# OLM-jee-128.net
KiCad netlist of a schematic drawn in EAGLE
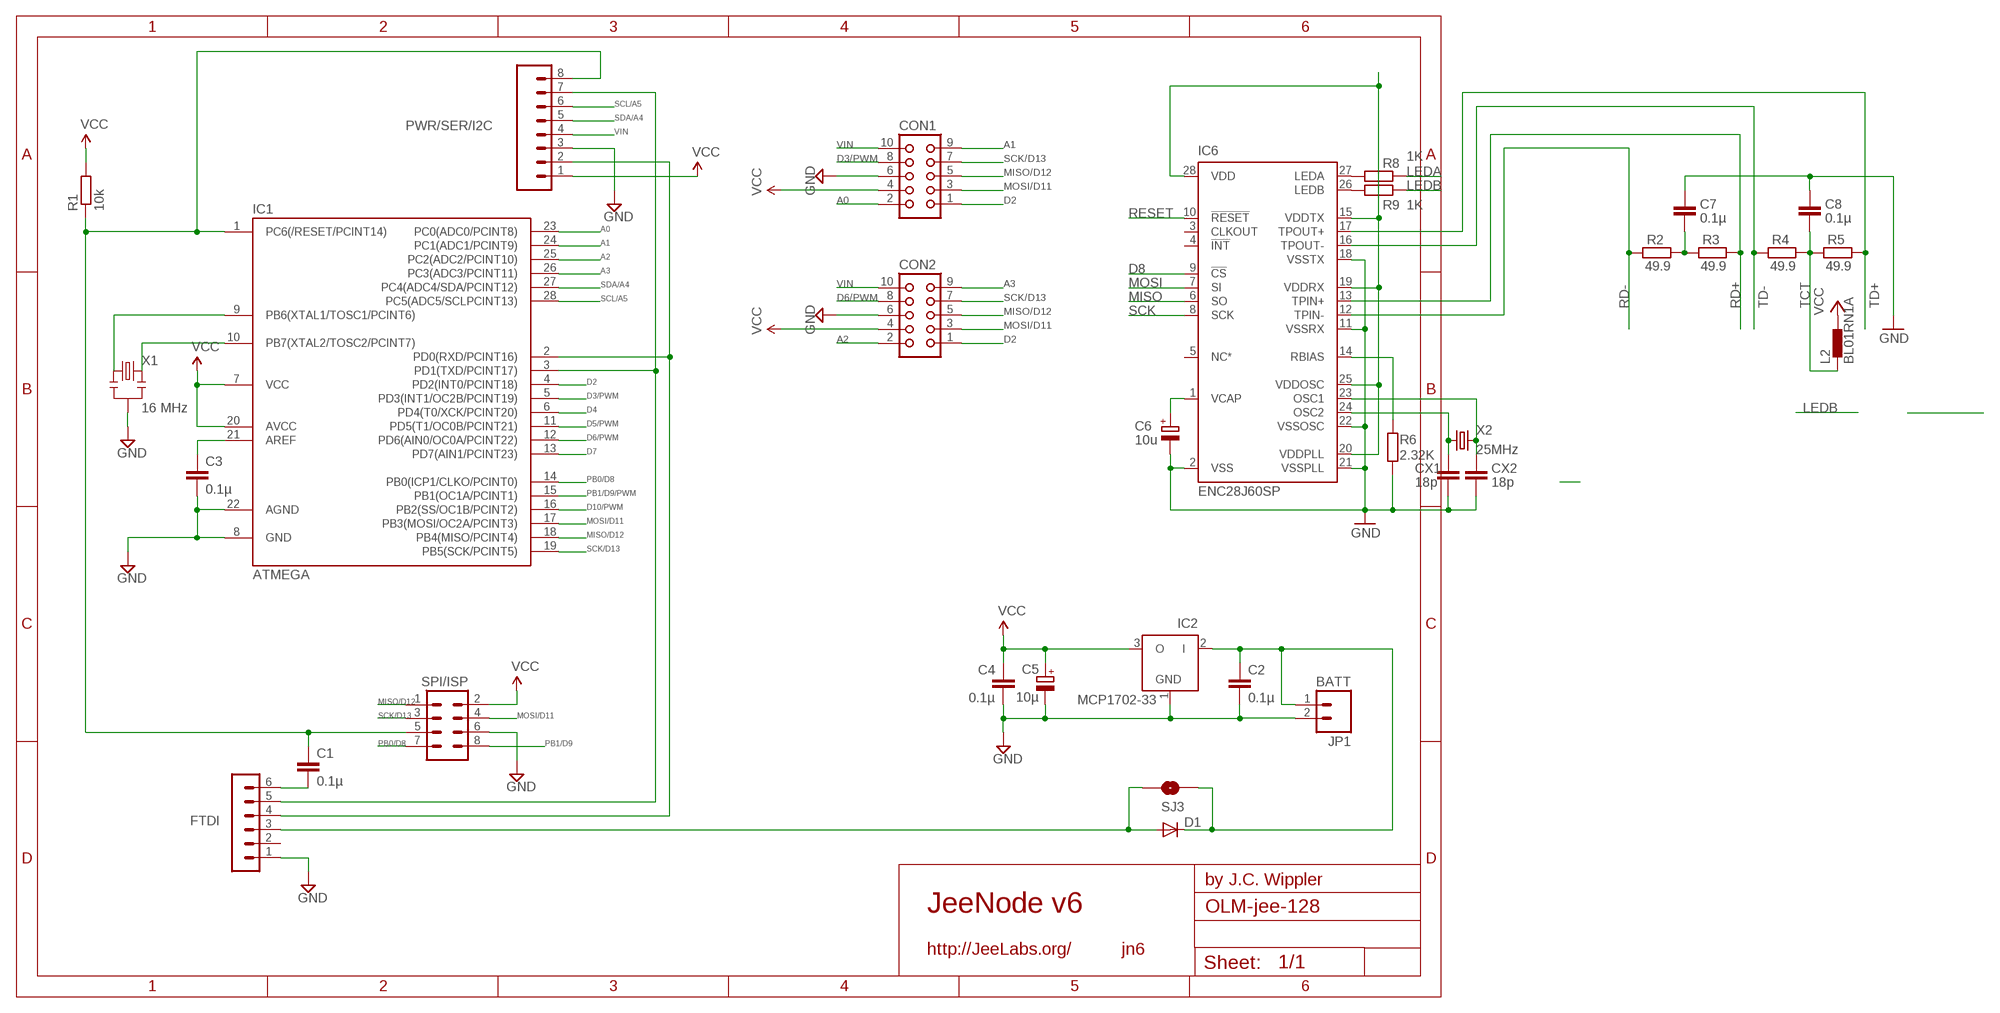
[diagram p0: schematic, sheet 1]

(export (version "E")
  (design (tool "Eeschema 10.0.6"))
  (components
    (comp (ref "C1")
      (value "0.1µ")
      (footprint "eagle-import:C025-024X044")
      (libsource (lib "eagle-import") (part "C-EU025-024X044"))
    )
    (comp (ref "C2")
      (value "0.1µ")
      (footprint "eagle-import:C025-024X044")
      (libsource (lib "eagle-import") (part "C-EU025-024X044"))
    )
    (comp (ref "C3")
      (value "0.1µ")
      (footprint "eagle-import:C025-024X044")
      (libsource (lib "eagle-import") (part "C-EU025-024X044"))
    )
    (comp (ref "C4")
      (value "0.1µ")
      (footprint "eagle-import:C025-024X044")
      (libsource (lib "eagle-import") (part "C-EU025-024X044"))
    )
    (comp (ref "C5")
      (value "10µ")
      (footprint "eagle-import:E1,8-4")
      (libsource (lib "eagle-import") (part "CPOL-EUE1.8-4"))
    )
    (comp (ref "C6")
      (value "10u")
      (footprint "eagle-import:E1,8-4")
      (libsource (lib "eagle-import") (part "CPOL-EUE1.8-4"))
    )
    (comp (ref "C7")
      (value "0.1µ")
      (footprint "eagle-import:C025-024X044")
      (libsource (lib "eagle-import") (part "C-EU025-024X044"))
    )
    (comp (ref "C8")
      (value "0.1µ")
      (footprint "eagle-import:C025-024X044")
      (libsource (lib "eagle-import") (part "C-EU025-024X044"))
    )
    (comp (ref "CON1")
      (value "CON10L")
      (footprint "eagle-import:CON10L")
      (libsource (lib "eagle-import") (part "CON10L"))
    )
    (comp (ref "CON2")
      (value "CON10L")
      (footprint "eagle-import:CON10L")
      (libsource (lib "eagle-import") (part "CON10L"))
    )
    (comp (ref "CX1")
      (value "18p")
      (footprint "eagle-import:C025-024X044")
      (libsource (lib "eagle-import") (part "C-EU025-024X044"))
    )
    (comp (ref "CX2")
      (value "18p")
      (footprint "eagle-import:C025-024X044")
      (libsource (lib "eagle-import") (part "C-EU025-024X044"))
    )
    (comp (ref "D1")
      (value "DIODE-D-5")
      (footprint "eagle-import:D-5")
      (libsource (lib "eagle-import") (part "DIODE-D-5"))
    )
    (comp (ref "FTDI")
      (value "FTDI")
      (footprint "eagle-import:MA06-1")
      (libsource (lib "eagle-import") (part "MA06-1"))
    )
    (comp (ref "IC1")
      (value "ATMEGA")
      (footprint "eagle-import:DIL28-3")
      (libsource (lib "eagle-import") (part "ATMEGA48/88/168-PU"))
    )
    (comp (ref "IC2")
      (value "MCP1702-33")
      (footprint "eagle-import:TO92")
      (libsource (lib "eagle-import") (part "MCP1702Z"))
    )
    (comp (ref "IC6")
      (value "ENC28J60SP")
      (footprint "eagle-import:DIL28-3")
      (fields (field (name "MF") "MICROCHIP") (field (name "MPN") "ENC28J60/SP"))
      (libsource (lib "eagle-import") (part "ENC28J60SP"))
    )
    (comp (ref "JP1")
      (value "BATT")
      (footprint "eagle-import:1X02_LOCK_LONGPADS")
      (libsource (lib "eagle-import") (part "M02LOCK_LONGPADS"))
    )
    (comp (ref "L2")
      (value "BL01RN1A")
      (footprint "eagle-import:BL01RN1A")
      (libsource (lib "eagle-import") (part "BL01RN1A"))
    )
    (comp (ref "PWR/SER/I2C")
      (value "M08")
      (footprint "eagle-import:1X08")
      (libsource (lib "eagle-import") (part "M08"))
    )
    (comp (ref "R1")
      (value "10k")
      (footprint "eagle-import:0204_7")
      (libsource (lib "eagle-import") (part "resistor_R-EU_0204/7"))
    )
    (comp (ref "R2")
      (value "49.9")
      (footprint "eagle-import:0204_7")
      (libsource (lib "eagle-import") (part "R-EU_0204/7"))
    )
    (comp (ref "R3")
      (value "49.9")
      (footprint "eagle-import:0204_7")
      (libsource (lib "eagle-import") (part "R-EU_0204/7"))
    )
    (comp (ref "R4")
      (value "49.9")
      (footprint "eagle-import:0204_7")
      (libsource (lib "eagle-import") (part "R-EU_0204/7"))
    )
    (comp (ref "R5")
      (value "49.9")
      (footprint "eagle-import:0204_7")
      (libsource (lib "eagle-import") (part "R-EU_0204/7"))
    )
    (comp (ref "R6")
      (value "2.32K")
      (footprint "eagle-import:0204_7")
      (libsource (lib "eagle-import") (part "R-EU_0204/7"))
    )
    (comp (ref "R8")
      (value "1K")
      (footprint "eagle-import:0204_7")
      (libsource (lib "eagle-import") (part "R-EU_0204/7"))
    )
    (comp (ref "R9")
      (value "1K")
      (footprint "eagle-import:0204_7")
      (libsource (lib "eagle-import") (part "R-EU_0204/7"))
    )
    (comp (ref "SJ3")
      (value "SOLDERJUMPERTRACE")
      (footprint "eagle-import:SJ_2S-TRACE")
      (libsource (lib "eagle-import") (part "SOLDERJUMPERTRACE"))
    )
    (comp (ref "SV7")
      (value "SPI/ISP")
      (footprint "eagle-import:MA04-2")
      (libsource (lib "eagle-import") (part "MA04-2"))
    )
    (comp (ref "X1")
      (value "16 MHz")
      (footprint "eagle-import:RESONATOR-PTH")
      (libsource (lib "eagle-import") (part "RESONATORPTH"))
    )
    (comp (ref "X2")
      (value "25MHz")
      (footprint "eagle-import:HC49US")
      (libsource (lib "eagle-import") (part "CRYSTALHC49US"))
    )
  )
  (nets
    (net (code "1") (name "/A0") (class "Default")
      (node (ref "CON1") (pin "2") (pinfunction "2_2") (pintype "passive"))
      (node (ref "IC1") (pin "23") (pinfunction "PC0(ADC0/PCINT8)_23") (pintype "bidirectional"))
    )
    (net (code "2") (name "/A1") (class "Default")
      (node (ref "CON1") (pin "9") (pinfunction "9_9") (pintype "passive"))
      (node (ref "IC1") (pin "24") (pinfunction "PC1(ADC1/PCINT9)_24") (pintype "bidirectional"))
    )
    (net (code "3") (name "/A2") (class "Default")
      (node (ref "CON2") (pin "2") (pinfunction "2_2") (pintype "passive"))
      (node (ref "IC1") (pin "25") (pinfunction "PC2(ADC2/PCINT10)_25") (pintype "bidirectional"))
    )
    (net (code "4") (name "/A3") (class "Default")
      (node (ref "CON2") (pin "9") (pinfunction "9_9") (pintype "passive"))
      (node (ref "IC1") (pin "26") (pinfunction "PC3(ADC3/PCINT11)_26") (pintype "bidirectional"))
    )
    (net (code "5") (name "/D2") (class "Default")
      (node (ref "CON1") (pin "1") (pinfunction "1_1") (pintype "passive"))
      (node (ref "CON2") (pin "1") (pinfunction "1_1") (pintype "passive"))
      (node (ref "IC1") (pin "4") (pinfunction "PD2(INT0/PCINT18)_4") (pintype "bidirectional"))
    )
    (net (code "6") (name "/D3{slash}PWM") (class "Default")
      (node (ref "CON1") (pin "8") (pinfunction "8_8") (pintype "passive"))
      (node (ref "IC1") (pin "5") (pinfunction "PD3(INT1/OC2B/PCINT19)_5") (pintype "bidirectional"))
    )
    (net (code "7") (name "/D4") (class "Default")
      (node (ref "IC1") (pin "6") (pinfunction "PD4(T0/XCK/PCINT20)_6") (pintype "bidirectional"))
    )
    (net (code "8") (name "/D5{slash}PWM") (class "Default")
      (node (ref "IC1") (pin "11") (pinfunction "PD5(T1/OC0B/PCINT21)_11") (pintype "bidirectional"))
    )
    (net (code "9") (name "/D6{slash}PWM") (class "Default")
      (node (ref "CON2") (pin "8") (pinfunction "8_8") (pintype "passive"))
      (node (ref "IC1") (pin "12") (pinfunction "PD6(AIN0/OC0A/PCINT22)_12") (pintype "bidirectional"))
    )
    (net (code "10") (name "/D7") (class "Default")
      (node (ref "IC1") (pin "13") (pinfunction "PD7(AIN1/PCINT23)_13") (pintype "bidirectional"))
    )
    (net (code "11") (name "/D8") (class "Default")
      (node (ref "IC6") (pin "9") (pinfunction "~{CS}_9") (pintype "input"))
    )
    (net (code "12") (name "/D10{slash}PWM") (class "Default")
      (node (ref "IC1") (pin "16") (pinfunction "PB2(SS/OC1B/PCINT2)_16") (pintype "bidirectional"))
    )
    (net (code "13") (name "/LEDA") (class "Default")
      (node (ref "R8") (pin "2") (pinfunction "2_2") (pintype "passive"))
    )
    (net (code "14") (name "/LEDB") (class "Default")
      (node (ref "R9") (pin "2") (pinfunction "2_2") (pintype "passive"))
    )
    (net (code "15") (name "/MISO") (class "Default")
      (node (ref "IC6") (pin "6") (pinfunction "SO_6") (pintype "output"))
    )
    (net (code "16") (name "/MISO{slash}D12") (class "Default")
      (node (ref "CON1") (pin "5") (pinfunction "5_5") (pintype "passive"))
      (node (ref "CON2") (pin "5") (pinfunction "5_5") (pintype "passive"))
      (node (ref "IC1") (pin "18") (pinfunction "PB4(MISO/PCINT4)_18") (pintype "bidirectional"))
      (node (ref "SV7") (pin "1") (pinfunction "1_1") (pintype "passive"))
    )
    (net (code "17") (name "/MOSI") (class "Default")
      (node (ref "IC6") (pin "7") (pinfunction "SI_7") (pintype "input"))
    )
    (net (code "18") (name "/MOSI{slash}D11") (class "Default")
      (node (ref "CON1") (pin "3") (pinfunction "3_3") (pintype "passive"))
      (node (ref "CON2") (pin "3") (pinfunction "3_3") (pintype "passive"))
      (node (ref "IC1") (pin "17") (pinfunction "PB3(MOSI/OC2A/PCINT3)_17") (pintype "bidirectional"))
      (node (ref "SV7") (pin "4") (pinfunction "4_4") (pintype "passive"))
    )
    (net (code "19") (name "/PB0{slash}D8") (class "Default")
      (node (ref "IC1") (pin "14") (pinfunction "PB0(ICP1/CLKO/PCINT0)_14") (pintype "bidirectional"))
      (node (ref "SV7") (pin "7") (pinfunction "7_7") (pintype "passive"))
    )
    (net (code "20") (name "/PB1{slash}D9") (class "Default")
      (node (ref "SV7") (pin "8") (pinfunction "8_8") (pintype "passive"))
    )
    (net (code "21") (name "/PB1{slash}D9{slash}PWM") (class "Default")
      (node (ref "IC1") (pin "15") (pinfunction "PB1(OC1A/PCINT1)_15") (pintype "bidirectional"))
    )
    (net (code "22") (name "/RD+") (class "Default")
      (node (ref "IC6") (pin "13") (pinfunction "TPIN+_13") (pintype "input"))
      (node (ref "R3") (pin "2") (pinfunction "2_2") (pintype "passive"))
    )
    (net (code "23") (name "/RD-") (class "Default")
      (node (ref "IC6") (pin "12") (pinfunction "TPIN-_12") (pintype "input"))
      (node (ref "R2") (pin "1") (pinfunction "1_1") (pintype "passive"))
    )
    (net (code "24") (name "/RESET") (class "Default")
      (node (ref "IC6") (pin "10") (pinfunction "~{RESET}_10") (pintype "input"))
    )
    (net (code "25") (name "/SCK") (class "Default")
      (node (ref "IC6") (pin "8") (pinfunction "SCK_8") (pintype "input"))
    )
    (net (code "26") (name "/SCK{slash}D13") (class "Default")
      (node (ref "CON1") (pin "7") (pinfunction "7_7") (pintype "passive"))
      (node (ref "CON2") (pin "7") (pinfunction "7_7") (pintype "passive"))
      (node (ref "IC1") (pin "19") (pinfunction "PB5(SCK/PCINT5)_19") (pintype "bidirectional"))
      (node (ref "SV7") (pin "3") (pinfunction "3_3") (pintype "passive"))
    )
    (net (code "27") (name "/SCL{slash}A5") (class "Default")
      (node (ref "IC1") (pin "28") (pinfunction "PC5(ADC5/SCLPCINT13)_28") (pintype "bidirectional"))
      (node (ref "PWR/SER/I2C") (pin "6") (pinfunction "6_6") (pintype "passive"))
    )
    (net (code "28") (name "/SDA{slash}A4") (class "Default")
      (node (ref "IC1") (pin "27") (pinfunction "PC4(ADC4/SDA/PCINT12)_27") (pintype "bidirectional"))
      (node (ref "PWR/SER/I2C") (pin "5") (pinfunction "5_5") (pintype "passive"))
    )
    (net (code "29") (name "/TCT") (class "Default")
      (node (ref "C8") (pin "2") (pinfunction "2_2") (pintype "passive"))
      (node (ref "L2") (pin "1") (pinfunction "1_1") (pintype "passive"))
      (node (ref "R4") (pin "2") (pinfunction "2_2") (pintype "passive"))
      (node (ref "R5") (pin "1") (pinfunction "1_1") (pintype "passive"))
    )
    (net (code "30") (name "/TD+") (class "Default")
      (node (ref "IC6") (pin "17") (pinfunction "TPOUT+_17") (pintype "output"))
      (node (ref "R5") (pin "2") (pinfunction "2_2") (pintype "passive"))
    )
    (net (code "31") (name "/TD-") (class "Default")
      (node (ref "IC6") (pin "16") (pinfunction "TPOUT-_16") (pintype "output"))
      (node (ref "R4") (pin "1") (pinfunction "1_1") (pintype "passive"))
    )
    (net (code "32") (name "/VIN") (class "Default")
      (node (ref "CON1") (pin "10") (pinfunction "10_10") (pintype "passive"))
      (node (ref "CON2") (pin "10") (pinfunction "10_10") (pintype "passive"))
      (node (ref "PWR/SER/I2C") (pin "4") (pinfunction "4_4") (pintype "passive"))
    )
    (net (code "33") (name "GND") (class "Default")
      (node (ref "C2") (pin "2") (pinfunction "2_2") (pintype "passive"))
      (node (ref "C3") (pin "2") (pinfunction "2_2") (pintype "passive"))
      (node (ref "C4") (pin "2") (pinfunction "2_2") (pintype "passive"))
      (node (ref "C5") (pin "-") (pinfunction "-_-") (pintype "passive"))
      (node (ref "C6") (pin "-") (pinfunction "-_-") (pintype "passive"))
      (node (ref "C7") (pin "1") (pinfunction "1_1") (pintype "passive"))
      (node (ref "C8") (pin "1") (pinfunction "1_1") (pintype "passive"))
      (node (ref "CON1") (pin "6") (pinfunction "6_6") (pintype "passive"))
      (node (ref "CON2") (pin "6") (pinfunction "6_6") (pintype "passive"))
      (node (ref "CX1") (pin "2") (pinfunction "2_2") (pintype "passive"))
      (node (ref "CX2") (pin "2") (pinfunction "2_2") (pintype "passive"))
      (node (ref "FTDI") (pin "1") (pinfunction "1_1") (pintype "passive"))
      (node (ref "IC1") (pin "22") (pinfunction "AGND_22") (pintype "power_in"))
      (node (ref "IC1") (pin "8") (pinfunction "GND_8") (pintype "power_in"))
      (node (ref "IC2") (pin "1") (pinfunction "GND_1") (pintype "power_in"))
      (node (ref "IC6") (pin "11") (pinfunction "VSSRX_11") (pintype "input"))
      (node (ref "IC6") (pin "18") (pinfunction "VSSTX_18") (pintype "input"))
      (node (ref "IC6") (pin "2") (pinfunction "VSS_2") (pintype "input"))
      (node (ref "IC6") (pin "21") (pinfunction "VSSPLL_21") (pintype "input"))
      (node (ref "IC6") (pin "22") (pinfunction "VSSOSC_22") (pintype "input"))
      (node (ref "JP1") (pin "2") (pinfunction "2_2") (pintype "passive"))
      (node (ref "PWR/SER/I2C") (pin "3") (pinfunction "3_3") (pintype "passive"))
      (node (ref "R6") (pin "2") (pinfunction "2_2") (pintype "passive"))
      (node (ref "SV7") (pin "6") (pinfunction "6_6") (pintype "passive"))
      (node (ref "X1") (pin "2") (pinfunction "2_2") (pintype "passive"))
    )
    (net (code "34") (name "Net-(C1-Pad2)") (class "Default")
      (node (ref "C1") (pin "2") (pinfunction "2_2") (pintype "passive"))
      (node (ref "FTDI") (pin "6") (pinfunction "6_6") (pintype "passive"))
    )
    (net (code "35") (name "Net-(C7-Pad2)") (class "Default")
      (node (ref "C7") (pin "2") (pinfunction "2_2") (pintype "passive"))
      (node (ref "R2") (pin "2") (pinfunction "2_2") (pintype "passive"))
      (node (ref "R3") (pin "1") (pinfunction "1_1") (pintype "passive"))
    )
    (net (code "36") (name "Net-(D1-PadA)") (class "Default")
      (node (ref "D1") (pin "A") (pinfunction "A_A") (pintype "passive"))
      (node (ref "FTDI") (pin "3") (pinfunction "3_3") (pintype "passive"))
      (node (ref "SJ3") (pin "2") (pinfunction "2_2") (pintype "passive"))
    )
    (net (code "37") (name "Net-(IC1-AREF)") (class "Default")
      (node (ref "C3") (pin "1") (pinfunction "1_1") (pintype "passive"))
      (node (ref "IC1") (pin "21") (pinfunction "AREF_21") (pintype "passive"))
    )
    (net (code "38") (name "Net-(IC1-PB6(XTAL1{slash}TOSC1{slash}PCINT6))") (class "Default")
      (node (ref "IC1") (pin "9") (pinfunction "PB6(XTAL1/TOSC1/PCINT6)_9") (pintype "bidirectional"))
      (node (ref "X1") (pin "1") (pinfunction "1_1") (pintype "passive"))
    )
    (net (code "39") (name "Net-(IC1-PB7(XTAL2{slash}TOSC2{slash}PCINT7))") (class "Default")
      (node (ref "IC1") (pin "10") (pinfunction "PB7(XTAL2/TOSC2/PCINT7)_10") (pintype "bidirectional"))
      (node (ref "X1") (pin "3") (pinfunction "3_3") (pintype "passive"))
    )
    (net (code "40") (name "Net-(IC1-PC6({slash}RESET{slash}PCINT14))") (class "Default")
      (node (ref "C1") (pin "1") (pinfunction "1_1") (pintype "passive"))
      (node (ref "IC1") (pin "1") (pinfunction "PC6(/RESET/PCINT14)_1") (pintype "bidirectional"))
      (node (ref "PWR/SER/I2C") (pin "8") (pinfunction "8_8") (pintype "passive"))
      (node (ref "R1") (pin "1") (pinfunction "1_1") (pintype "passive"))
      (node (ref "SV7") (pin "5") (pinfunction "5_5") (pintype "passive"))
    )
    (net (code "41") (name "Net-(IC1-PD0(RXD{slash}PCINT16))") (class "Default")
      (node (ref "FTDI") (pin "4") (pinfunction "4_4") (pintype "passive"))
      (node (ref "IC1") (pin "2") (pinfunction "PD0(RXD/PCINT16)_2") (pintype "bidirectional"))
      (node (ref "PWR/SER/I2C") (pin "2") (pinfunction "2_2") (pintype "passive"))
    )
    (net (code "42") (name "Net-(IC1-PD1(TXD{slash}PCINT17))") (class "Default")
      (node (ref "FTDI") (pin "5") (pinfunction "5_5") (pintype "passive"))
      (node (ref "IC1") (pin "3") (pinfunction "PD1(TXD/PCINT17)_3") (pintype "bidirectional"))
      (node (ref "PWR/SER/I2C") (pin "7") (pinfunction "7_7") (pintype "passive"))
    )
    (net (code "43") (name "Net-(IC2-I)") (class "Default")
      (node (ref "C2") (pin "1") (pinfunction "1_1") (pintype "passive"))
      (node (ref "D1") (pin "C") (pinfunction "C_C") (pintype "passive"))
      (node (ref "IC2") (pin "2") (pinfunction "I_2") (pintype "input"))
      (node (ref "JP1") (pin "1") (pinfunction "1_1") (pintype "passive"))
      (node (ref "SJ3") (pin "1") (pinfunction "1_1") (pintype "passive"))
    )
    (net (code "44") (name "Net-(IC6-LEDA)") (class "Default")
      (node (ref "IC6") (pin "27") (pinfunction "LEDA_27") (pintype "output"))
      (node (ref "R8") (pin "1") (pinfunction "1_1") (pintype "passive"))
    )
    (net (code "45") (name "Net-(IC6-LEDB)") (class "Default")
      (node (ref "IC6") (pin "26") (pinfunction "LEDB_26") (pintype "output"))
      (node (ref "R9") (pin "1") (pinfunction "1_1") (pintype "passive"))
    )
    (net (code "46") (name "Net-(IC6-OSC1)") (class "Default")
      (node (ref "CX2") (pin "1") (pinfunction "1_1") (pintype "passive"))
      (node (ref "IC6") (pin "23") (pinfunction "OSC1_23") (pintype "input"))
      (node (ref "X2") (pin "2") (pinfunction "2_2") (pintype "passive"))
    )
    (net (code "47") (name "Net-(IC6-OSC2)") (class "Default")
      (node (ref "CX1") (pin "1") (pinfunction "1_1") (pintype "passive"))
      (node (ref "IC6") (pin "24") (pinfunction "OSC2_24") (pintype "output"))
      (node (ref "X2") (pin "1") (pinfunction "1_1") (pintype "passive"))
    )
    (net (code "48") (name "Net-(IC6-RBIAS)") (class "Default")
      (node (ref "IC6") (pin "14") (pinfunction "RBIAS_14") (pintype "input"))
      (node (ref "R6") (pin "1") (pinfunction "1_1") (pintype "passive"))
    )
    (net (code "49") (name "Net-(IC6-VCAP)") (class "Default")
      (node (ref "C6") (pin "+") (pinfunction "+_+") (pintype "passive"))
      (node (ref "IC6") (pin "1") (pinfunction "VCAP_1") (pintype "input"))
    )
    (net (code "50") (name "VCC") (class "Default")
      (node (ref "C4") (pin "1") (pinfunction "1_1") (pintype "passive"))
      (node (ref "C5") (pin "+") (pinfunction "+_+") (pintype "passive"))
      (node (ref "CON1") (pin "4") (pinfunction "4_4") (pintype "passive"))
      (node (ref "CON2") (pin "4") (pinfunction "4_4") (pintype "passive"))
      (node (ref "IC1") (pin "20") (pinfunction "AVCC_20") (pintype "passive"))
      (node (ref "IC1") (pin "7") (pinfunction "VCC_7") (pintype "power_in"))
      (node (ref "IC2") (pin "3") (pinfunction "O_3") (pintype "input"))
      (node (ref "IC6") (pin "15") (pinfunction "VDDTX_15") (pintype "input"))
      (node (ref "IC6") (pin "19") (pinfunction "VDDRX_19") (pintype "input"))
      (node (ref "IC6") (pin "20") (pinfunction "VDDPLL_20") (pintype "input"))
      (node (ref "IC6") (pin "25") (pinfunction "VDDOSC_25") (pintype "input"))
      (node (ref "IC6") (pin "28") (pinfunction "VDD_28") (pintype "input"))
      (node (ref "L2") (pin "2") (pinfunction "2_2") (pintype "passive"))
      (node (ref "PWR/SER/I2C") (pin "1") (pinfunction "1_1") (pintype "passive"))
      (node (ref "R1") (pin "2") (pinfunction "2_2") (pintype "passive"))
      (node (ref "SV7") (pin "2") (pinfunction "2_2") (pintype "passive"))
    )
    (net (code "51") (name "unconnected-(FTDI-Pad2)") (class "Default")
      (node (ref "FTDI") (pin "2") (pinfunction "2_2") (pintype "passive"))
    )
    (net (code "52") (name "unconnected-(IC6-CLKOUT-Pad3)") (class "Default")
      (node (ref "IC6") (pin "3") (pinfunction "CLKOUT_3") (pintype "output"))
    )
    (net (code "53") (name "unconnected-(IC6-NC*-Pad5)") (class "Default")
      (node (ref "IC6") (pin "5") (pinfunction "NC*_5") (pintype "output"))
    )
    (net (code "54") (name "unconnected-(IC6-~{INT}-Pad4)") (class "Default")
      (node (ref "IC6") (pin "4") (pinfunction "~{INT}_4") (pintype "output"))
    )
  )
)
